# A4a_ESP32-S3-WROOM-1_1_0.net
KiCad netlist of a schematic drawn in EAGLE
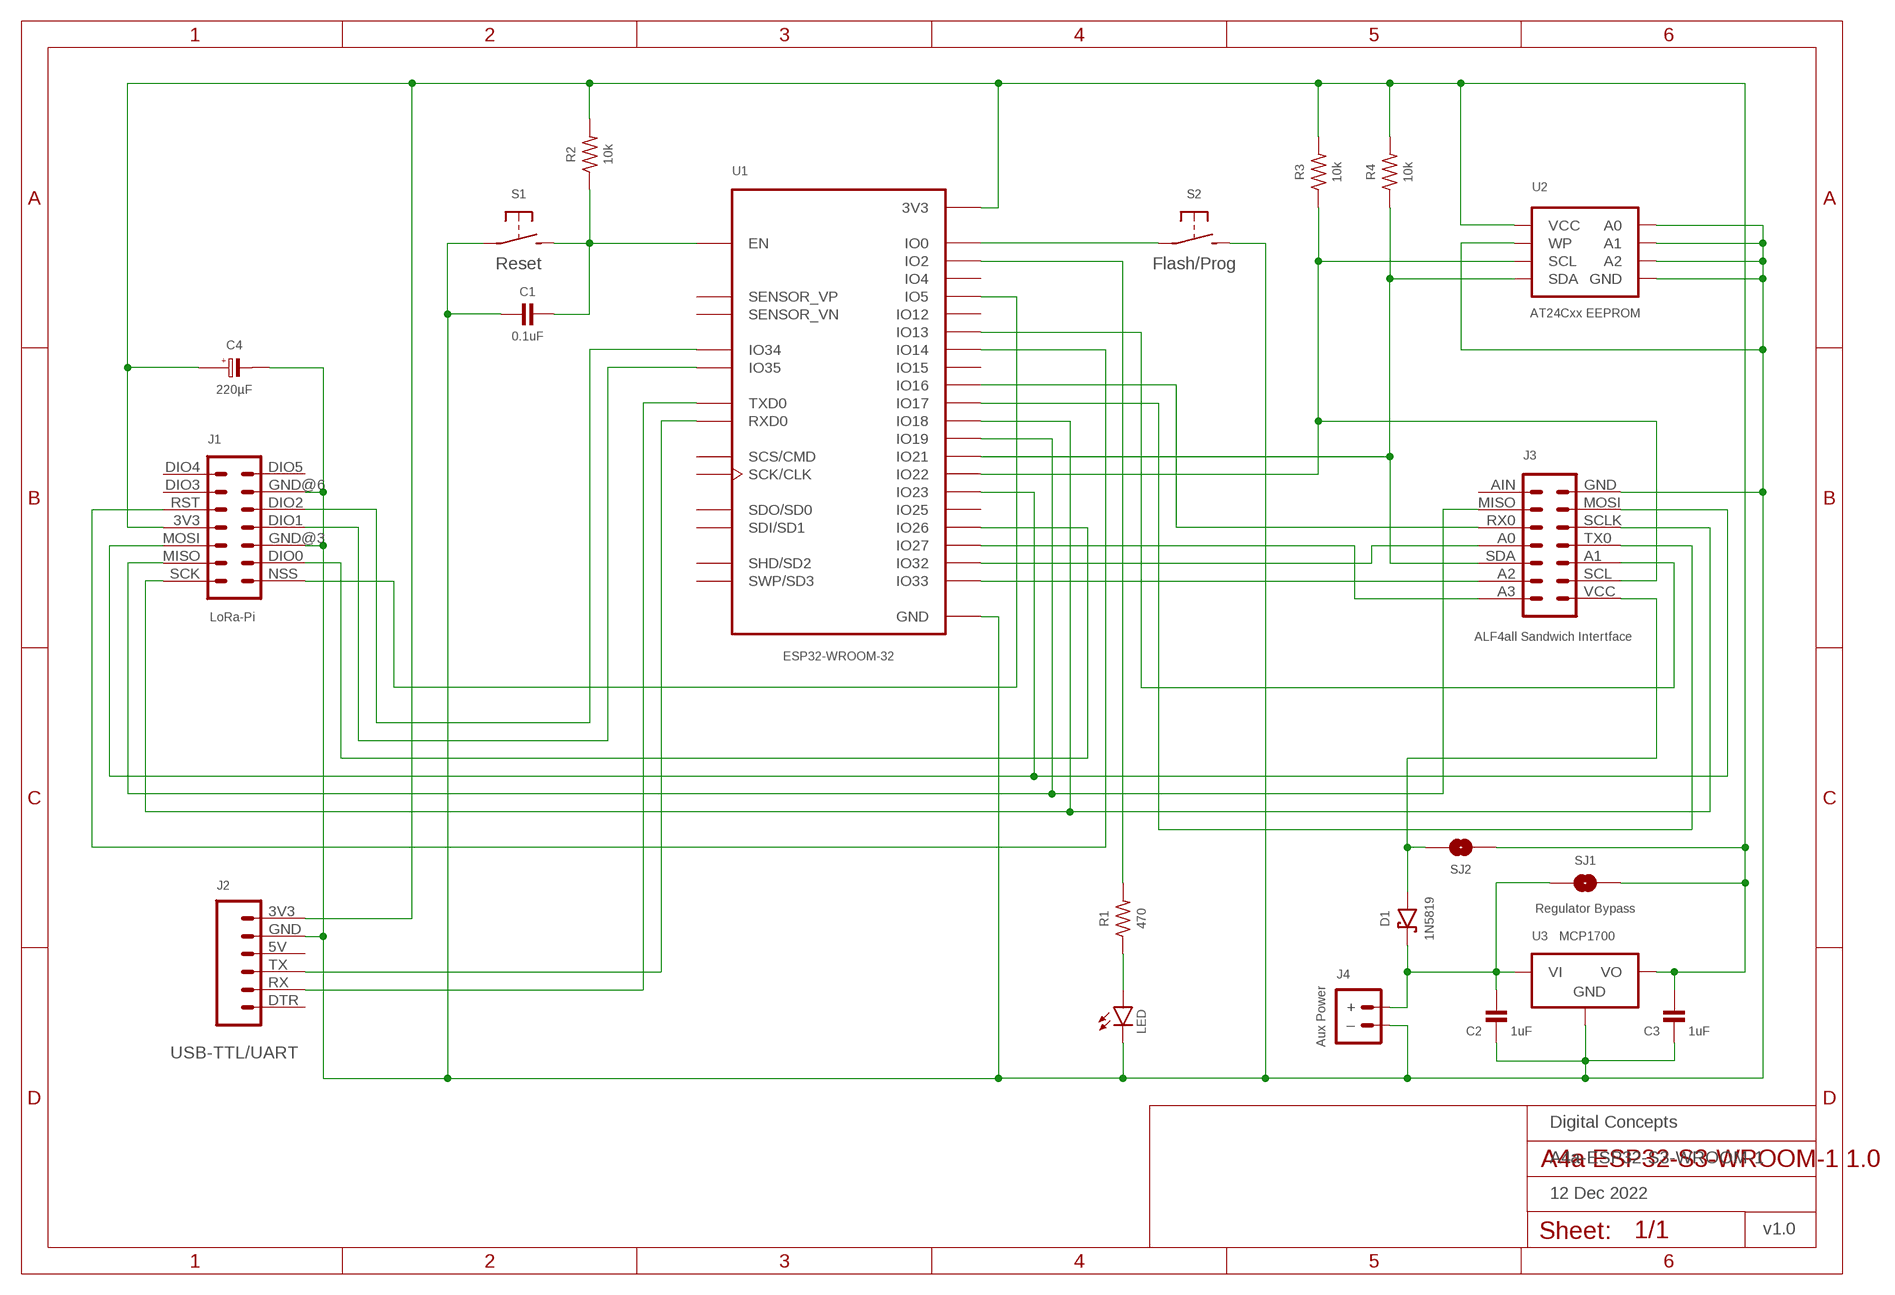
[diagram p0: schematic, sheet 1]

(export (version "E")
  (design (tool "Eeschema 10.0.6"))
  (components
    (comp (ref "C1")
      (value "0.1uF")
      (footprint "eagle-import:C0805@1")
      (libsource (lib "eagle-import") (part "CAPACITOR"))
    )
    (comp (ref "C2")
      (value "1uF")
      (footprint "eagle-import:C0805@1")
      (libsource (lib "eagle-import") (part "CAPACITOR"))
    )
    (comp (ref "C3")
      (value "1uF")
      (footprint "eagle-import:C0805@1")
      (libsource (lib "eagle-import") (part "CAPACITOR"))
    )
    (comp (ref "C4")
      (value "220µF")
      (footprint "eagle-import:C3528-21")
      (libsource (lib "eagle-import") (part "CAPACITOR-TANTALUM-3528"))
    )
    (comp (ref "D1")
      (value "1N5819")
      (footprint "eagle-import:SOD-123")
      (libsource (lib "eagle-import") (part "DIODE-SCHOTTKY-1N5819"))
    )
    (comp (ref "J1")
      (value "LoRa-Pi")
      (footprint "eagle-import:RFM95W-PI")
      (libsource (lib "eagle-import") (part "RFM95W-PI-HEADER"))
    )
    (comp (ref "J2")
      (value "USB-TTL/UART")
      (footprint "eagle-import:CONN_06-UART")
      (libsource (lib "eagle-import") (part "HEADER-1X6-UART"))
    )
    (comp (ref "J3")
      (value "ALF4all Sandwich Intertface")
      (footprint "eagle-import:CONN_2X7-ALF4ALL-PROCESSOR-B")
      (libsource (lib "eagle-import") (part "HEADER-2X7-ALF4ALL-PROCESSOR-B"))
    )
    (comp (ref "J4")
      (value "Aux Power")
      (footprint "eagle-import:JST-PH2.0-2-HORIZONTAL")
      (libsource (lib "eagle-import") (part "JST-PH2.0-2-MALE-HORIZONTALJST-PTH-2"))
    )
    (comp (ref "LED")
      (value "LEDCHIP-LED0805")
      (footprint "eagle-import:CHIP-LED0805")
      (libsource (lib "eagle-import") (part "LEDCHIP-LED0805"))
    )
    (comp (ref "R1")
      (value "470")
      (footprint "eagle-import:R0805")
      (libsource (lib "eagle-import") (part "RESISTORR0805"))
    )
    (comp (ref "R2")
      (value "10k")
      (footprint "eagle-import:R0805")
      (libsource (lib "eagle-import") (part "RESISTORR0805"))
    )
    (comp (ref "R3")
      (value "10k")
      (footprint "eagle-import:R0805")
      (libsource (lib "eagle-import") (part "RESISTORR0805"))
    )
    (comp (ref "R4")
      (value "10k")
      (footprint "eagle-import:R0805")
      (libsource (lib "eagle-import") (part "RESISTORR0805"))
    )
    (comp (ref "S1")
      (value "Reset")
      (footprint "eagle-import:SWITCH-2-PAD")
      (libsource (lib "eagle-import") (part "SWITCH-MOMENTARY-2-PIN"))
    )
    (comp (ref "S2")
      (value "Flash/Prog")
      (footprint "eagle-import:SWITCH-2-PAD")
      (libsource (lib "eagle-import") (part "SWITCH-MOMENTARY-2-PIN"))
    )
    (comp (ref "SJ1")
      (value "Regulator Bypass")
      (footprint "eagle-import:SJ")
      (libsource (lib "eagle-import") (part "SJ"))
    )
    (comp (ref "SJ2") (value "SJ") (footprint "eagle-import:SJ") (libsource (lib "eagle-import") (part "SJ")))
    (comp (ref "U1")
      (value "ESP32-WROOM-32")
      (footprint "eagle-import:ESP32-WROOM-32")
      (libsource (lib "eagle-import") (part "ESP32-WROOM-32"))
    )
    (comp (ref "U2")
      (value "AT24Cxx EEPROM")
      (footprint "eagle-import:SOP-8")
      (libsource (lib "eagle-import") (part "AT24CXX-EEPROM"))
    )
    (comp (ref "U3")
      (value "MCP1700")
      (footprint "eagle-import:SOT-23-3")
      (libsource (lib "eagle-import") (part "MCP1700"))
    )
  )
  (nets
    (net (code "1") (name "Net-(C4-+)") (class "Default")
      (node (ref "C3") (pin "1") (pinfunction "1_1") (pintype "passive"))
      (node (ref "C4") (pin "1") (pinfunction "+_1") (pintype "passive"))
      (node (ref "J1") (pin "3V3") (pinfunction "11_3V3") (pintype "passive"))
      (node (ref "J2") (pin "3V3") (pinfunction "6_3V3") (pintype "passive"))
      (node (ref "R2") (pin "2") (pinfunction "2_2") (pintype "passive"))
      (node (ref "R3") (pin "2") (pinfunction "2_2") (pintype "passive"))
      (node (ref "R4") (pin "2") (pinfunction "2_2") (pintype "passive"))
      (node (ref "SJ1") (pin "2") (pinfunction "2_2") (pintype "passive"))
      (node (ref "SJ2") (pin "2") (pinfunction "2_2") (pintype "passive"))
      (node (ref "U1") (pin "3V3") (pinfunction "3V3_3V3") (pintype "power_in"))
      (node (ref "U2") (pin "P$8") (pinfunction "VCC_P$8") (pintype "bidirectional"))
      (node (ref "U3") (pin "2") (pinfunction "VO_2") (pintype "output"))
    )
    (net (code "2") (name "Net-(C4--)") (class "Default")
      (node (ref "C1") (pin "2") (pinfunction "2_2") (pintype "passive"))
      (node (ref "C2") (pin "2") (pinfunction "2_2") (pintype "passive"))
      (node (ref "C3") (pin "2") (pinfunction "2_2") (pintype "passive"))
      (node (ref "C4") (pin "2") (pinfunction "-_2") (pintype "passive"))
      (node (ref "J1") (pin "GND@3") (pinfunction "3_GND@3") (pintype "passive"))
      (node (ref "J1") (pin "GND@6") (pinfunction "6_GND@6") (pintype "passive"))
      (node (ref "J2") (pin "GND") (pinfunction "5_GND") (pintype "passive"))
      (node (ref "J3") (pin "GND") (pinfunction "7_GND") (pintype "passive"))
      (node (ref "J4") (pin "-") (pinfunction "–_-") (pintype "power_in"))
      (node (ref "LED") (pin "C") (pinfunction "C_C") (pintype "passive"))
      (node (ref "S1") (pin "P$1") (pinfunction "P_P$1") (pintype "passive"))
      (node (ref "S2") (pin "P$2") (pinfunction "S_P$2") (pintype "passive"))
      (node (ref "U1") (pin "GND@1") (pinfunction "GND_GND@1") (pintype "power_in"))
      (node (ref "U1") (pin "GND@15") (pinfunction "GND_GND@15") (pintype "power_in"))
      (node (ref "U1") (pin "GND@38") (pinfunction "GND_GND@38") (pintype "power_in"))
      (node (ref "U1") (pin "TP") (pinfunction "GND_TP") (pintype "power_in"))
      (node (ref "U1") (pin "TP@P1") (pinfunction "GND_TP@P1") (pintype "power_in"))
      (node (ref "U1") (pin "TP@P2") (pinfunction "GND_TP@P2") (pintype "power_in"))
      (node (ref "U1") (pin "TP@P3") (pinfunction "GND_TP@P3") (pintype "power_in"))
      (node (ref "U1") (pin "TP@P4") (pinfunction "GND_TP@P4") (pintype "power_in"))
      (node (ref "U1") (pin "TP@P5") (pinfunction "GND_TP@P5") (pintype "power_in"))
      (node (ref "U1") (pin "TP@P6") (pinfunction "GND_TP@P6") (pintype "power_in"))
      (node (ref "U1") (pin "TP@P7") (pinfunction "GND_TP@P7") (pintype "power_in"))
      (node (ref "U1") (pin "TP@P8") (pinfunction "GND_TP@P8") (pintype "power_in"))
      (node (ref "U1") (pin "TP@P9") (pinfunction "GND_TP@P9") (pintype "power_in"))
      (node (ref "U1") (pin "TP@V1") (pinfunction "GND_TP@V1") (pintype "power_in"))
      (node (ref "U1") (pin "TP@V10") (pinfunction "GND_TP@V10") (pintype "power_in"))
      (node (ref "U1") (pin "TP@V11") (pinfunction "GND_TP@V11") (pintype "power_in"))
      (node (ref "U1") (pin "TP@V12") (pinfunction "GND_TP@V12") (pintype "power_in"))
      (node (ref "U1") (pin "TP@V2") (pinfunction "GND_TP@V2") (pintype "power_in"))
      (node (ref "U1") (pin "TP@V3") (pinfunction "GND_TP@V3") (pintype "power_in"))
      (node (ref "U1") (pin "TP@V4") (pinfunction "GND_TP@V4") (pintype "power_in"))
      (node (ref "U1") (pin "TP@V5") (pinfunction "GND_TP@V5") (pintype "power_in"))
      (node (ref "U1") (pin "TP@V6") (pinfunction "GND_TP@V6") (pintype "power_in"))
      (node (ref "U1") (pin "TP@V7") (pinfunction "GND_TP@V7") (pintype "power_in"))
      (node (ref "U1") (pin "TP@V8") (pinfunction "GND_TP@V8") (pintype "power_in"))
      (node (ref "U1") (pin "TP@V9") (pinfunction "GND_TP@V9") (pintype "power_in"))
      (node (ref "U1") (pin "TP@VP5") (pinfunction "GND_TP@VP5") (pintype "power_in"))
      (node (ref "U2") (pin "P$1") (pinfunction "A0_P$1") (pintype "bidirectional"))
      (node (ref "U2") (pin "P$2") (pinfunction "A1_P$2") (pintype "bidirectional"))
      (node (ref "U2") (pin "P$3") (pinfunction "A2_P$3") (pintype "bidirectional"))
      (node (ref "U2") (pin "P$4") (pinfunction "GND_P$4") (pintype "bidirectional"))
      (node (ref "U2") (pin "P$7") (pinfunction "WP_P$7") (pintype "bidirectional"))
      (node (ref "U3") (pin "1") (pinfunction "GND_1") (pintype "passive"))
    )
    (net (code "3") (name "Net-(J1-1)") (class "Default")
      (node (ref "J1") (pin "NSS") (pinfunction "1_NSS") (pintype "passive"))
      (node (ref "U1") (pin "IO5") (pinfunction "IO5_IO5") (pintype "bidirectional"))
    )
    (net (code "4") (name "Net-(J1-2)") (class "Default")
      (node (ref "J1") (pin "DIO0") (pinfunction "2_DIO0") (pintype "passive"))
      (node (ref "U1") (pin "IO26") (pinfunction "IO26_IO26") (pintype "bidirectional"))
    )
    (net (code "5") (name "Net-(J1-4)") (class "Default")
      (node (ref "J1") (pin "DIO1") (pinfunction "4_DIO1") (pintype "passive"))
      (node (ref "U1") (pin "IO35") (pinfunction "IO35_IO35") (pintype "input"))
    )
    (net (code "6") (name "Net-(J1-5)") (class "Default")
      (node (ref "J1") (pin "DIO2") (pinfunction "5_DIO2") (pintype "passive"))
      (node (ref "U1") (pin "IO34") (pinfunction "IO34_IO34") (pintype "input"))
    )
    (net (code "7") (name "Net-(J1-10)") (class "Default")
      (node (ref "J1") (pin "RST") (pinfunction "10_RST") (pintype "passive"))
      (node (ref "U1") (pin "IO14") (pinfunction "IO14_IO14") (pintype "bidirectional"))
    )
    (net (code "8") (name "Net-(J1-12)") (class "Default")
      (node (ref "J1") (pin "MOSI") (pinfunction "12_MOSI") (pintype "passive"))
      (node (ref "J3") (pin "MOSI") (pinfunction "6_MOSI") (pintype "passive"))
      (node (ref "U1") (pin "IO23") (pinfunction "IO23_IO23") (pintype "bidirectional"))
    )
    (net (code "9") (name "Net-(J1-13)") (class "Default")
      (node (ref "J1") (pin "MISO") (pinfunction "13_MISO") (pintype "passive"))
      (node (ref "J3") (pin "MISO") (pinfunction "9_MISO") (pintype "passive"))
      (node (ref "U1") (pin "IO19") (pinfunction "IO19_IO19") (pintype "bidirectional"))
    )
    (net (code "10") (name "Net-(J1-14)") (class "Default")
      (node (ref "J1") (pin "SCK") (pinfunction "14_SCK") (pintype "passive"))
      (node (ref "J3") (pin "SCLK") (pinfunction "5_SCLK") (pintype "passive"))
      (node (ref "U1") (pin "IO18") (pinfunction "IO18_IO18") (pintype "bidirectional"))
    )
    (net (code "11") (name "Net-(J2-2)") (class "Default")
      (node (ref "J2") (pin "RX") (pinfunction "2_RX") (pintype "passive"))
      (node (ref "U1") (pin "TXD0") (pinfunction "TXD0_TXD0") (pintype "bidirectional"))
    )
    (net (code "12") (name "Net-(J2-3)") (class "Default")
      (node (ref "J2") (pin "TX") (pinfunction "3_TX") (pintype "passive"))
      (node (ref "U1") (pin "RXD0") (pinfunction "RXD0_RXD0") (pintype "bidirectional"))
    )
    (net (code "13") (name "Net-(J3-1)") (class "Default")
      (node (ref "D1") (pin "A") (pinfunction "A_A") (pintype "passive"))
      (node (ref "J3") (pin "VCC") (pinfunction "1_VCC") (pintype "passive"))
      (node (ref "SJ2") (pin "1") (pinfunction "1_1") (pintype "passive"))
    )
    (net (code "14") (name "Net-(J3-2)") (class "Default")
      (node (ref "J3") (pin "SCL") (pinfunction "2_SCL") (pintype "passive"))
      (node (ref "R3") (pin "1") (pinfunction "1_1") (pintype "passive"))
      (node (ref "U1") (pin "IO22") (pinfunction "IO22_IO22") (pintype "bidirectional"))
      (node (ref "U2") (pin "P$6") (pinfunction "SCL_P$6") (pintype "bidirectional"))
    )
    (net (code "15") (name "Net-(J3-3)") (class "Default")
      (node (ref "J3") (pin "A1") (pinfunction "3_A1") (pintype "passive"))
      (node (ref "U1") (pin "IO13") (pinfunction "IO13_IO13") (pintype "bidirectional"))
    )
    (net (code "16") (name "Net-(J3-4)") (class "Default")
      (node (ref "J3") (pin "TX0") (pinfunction "4_TX0") (pintype "passive"))
      (node (ref "U1") (pin "IO17") (pinfunction "IO17_IO17") (pintype "bidirectional"))
    )
    (net (code "17") (name "Net-(J3-10)") (class "Default")
      (node (ref "J3") (pin "RX0") (pinfunction "10_RX0") (pintype "passive"))
      (node (ref "U1") (pin "IO16") (pinfunction "IO16_IO16") (pintype "bidirectional"))
    )
    (net (code "18") (name "Net-(J3-11)") (class "Default")
      (node (ref "J3") (pin "A0") (pinfunction "11_A0") (pintype "passive"))
      (node (ref "U1") (pin "IO32") (pinfunction "IO32_IO32") (pintype "bidirectional"))
    )
    (net (code "19") (name "Net-(J3-12)") (class "Default")
      (node (ref "J3") (pin "SDA") (pinfunction "12_SDA") (pintype "passive"))
      (node (ref "R4") (pin "1") (pinfunction "1_1") (pintype "passive"))
      (node (ref "U1") (pin "IO21") (pinfunction "IO21_IO21") (pintype "bidirectional"))
      (node (ref "U2") (pin "P$5") (pinfunction "SDA_P$5") (pintype "bidirectional"))
    )
    (net (code "20") (name "Net-(J3-13)") (class "Default")
      (node (ref "J3") (pin "A2") (pinfunction "13_A2") (pintype "passive"))
      (node (ref "U1") (pin "IO33") (pinfunction "IO33_IO33") (pintype "bidirectional"))
    )
    (net (code "21") (name "Net-(J3-14)") (class "Default")
      (node (ref "J3") (pin "A3") (pinfunction "14_A3") (pintype "passive"))
      (node (ref "U1") (pin "IO27") (pinfunction "IO27_IO27") (pintype "bidirectional"))
    )
    (net (code "22") (name "Net-(LED-PadA)") (class "Default")
      (node (ref "LED") (pin "A") (pinfunction "A_A") (pintype "passive"))
      (node (ref "R1") (pin "1") (pinfunction "1_1") (pintype "passive"))
    )
    (net (code "23") (name "Net-(R1-Pad2)") (class "Default")
      (node (ref "R1") (pin "2") (pinfunction "2_2") (pintype "passive"))
      (node (ref "U1") (pin "IO2") (pinfunction "IO2_IO2") (pintype "bidirectional"))
    )
    (net (code "24") (name "Net-(S1-S)") (class "Default")
      (node (ref "C1") (pin "1") (pinfunction "1_1") (pintype "passive"))
      (node (ref "R2") (pin "1") (pinfunction "1_1") (pintype "passive"))
      (node (ref "S1") (pin "P$2") (pinfunction "S_P$2") (pintype "passive"))
      (node (ref "U1") (pin "EN") (pinfunction "EN_EN") (pintype "input"))
    )
    (net (code "25") (name "Net-(S2-P)") (class "Default")
      (node (ref "S2") (pin "P$1") (pinfunction "P_P$1") (pintype "passive"))
      (node (ref "U1") (pin "IO0") (pinfunction "IO0_IO0") (pintype "bidirectional"))
    )
    (net (code "26") (name "Net-(U3-VI)") (class "Default")
      (node (ref "C2") (pin "1") (pinfunction "1_1") (pintype "passive"))
      (node (ref "D1") (pin "C") (pinfunction "C_C") (pintype "passive"))
      (node (ref "J4") (pin "+") (pinfunction "+_+") (pintype "power_in"))
      (node (ref "SJ1") (pin "1") (pinfunction "1_1") (pintype "passive"))
      (node (ref "U3") (pin "3") (pinfunction "VI_3") (pintype "input"))
    )
    (net (code "27") (name "unconnected-(J1-7-PadDIO5)") (class "Default")
      (node (ref "J1") (pin "DIO5") (pinfunction "7_DIO5") (pintype "passive"))
    )
    (net (code "28") (name "unconnected-(J1-8-PadDIO4)") (class "Default")
      (node (ref "J1") (pin "DIO4") (pinfunction "8_DIO4") (pintype "passive"))
    )
    (net (code "29") (name "unconnected-(J1-9-PadDIO3)") (class "Default")
      (node (ref "J1") (pin "DIO3") (pinfunction "9_DIO3") (pintype "passive"))
    )
    (net (code "30") (name "unconnected-(J2-1-PadDTR)") (class "Default")
      (node (ref "J2") (pin "DTR") (pinfunction "1_DTR") (pintype "passive"))
    )
    (net (code "31") (name "unconnected-(J2-4-Pad5V)") (class "Default")
      (node (ref "J2") (pin "5V") (pinfunction "4_5V") (pintype "passive"))
    )
    (net (code "32") (name "unconnected-(J3-8-PadAIN)") (class "Default")
      (node (ref "J3") (pin "AIN") (pinfunction "8_AIN") (pintype "passive"))
    )
    (net (code "33") (name "unconnected-(U1-PadIO4)") (class "Default")
      (node (ref "U1") (pin "IO4") (pinfunction "IO4_IO4") (pintype "bidirectional"))
    )
    (net (code "34") (name "unconnected-(U1-PadIO12)") (class "Default")
      (node (ref "U1") (pin "IO12") (pinfunction "IO12_IO12") (pintype "bidirectional"))
    )
    (net (code "35") (name "unconnected-(U1-PadIO15)") (class "Default")
      (node (ref "U1") (pin "IO15") (pinfunction "IO15_IO15") (pintype "bidirectional"))
    )
    (net (code "36") (name "unconnected-(U1-PadIO25)") (class "Default")
      (node (ref "U1") (pin "IO25") (pinfunction "IO25_IO25") (pintype "bidirectional"))
    )
    (net (code "37") (name "unconnected-(U1-PadSENSOR_VN)") (class "Default")
      (node (ref "U1") (pin "SENSOR_VN") (pinfunction "SENSOR_VN_SENSOR_VN") (pintype "input"))
    )
    (net (code "38") (name "unconnected-(U1-PadSENSOR_VP)") (class "Default")
      (node (ref "U1") (pin "SENSOR_VP") (pinfunction "SENSOR_VP_SENSOR_VP") (pintype "input"))
    )
    (net (code "39") (name "unconnected-(U1-SCK{slash}CLK-PadCLK)") (class "Default")
      (node (ref "U1") (pin "CLK") (pinfunction "SCK/CLK_CLK") (pintype "bidirectional"))
    )
    (net (code "40") (name "unconnected-(U1-SCS{slash}CMD-PadCMD)") (class "Default")
      (node (ref "U1") (pin "CMD") (pinfunction "SCS/CMD_CMD") (pintype "bidirectional"))
    )
    (net (code "41") (name "unconnected-(U1-SDI{slash}SD1-PadSD1)") (class "Default")
      (node (ref "U1") (pin "SD1") (pinfunction "SDI/SD1_SD1") (pintype "bidirectional"))
    )
    (net (code "42") (name "unconnected-(U1-SDO{slash}SD0-PadSD0)") (class "Default")
      (node (ref "U1") (pin "SD0") (pinfunction "SDO/SD0_SD0") (pintype "bidirectional"))
    )
    (net (code "43") (name "unconnected-(U1-SHD{slash}SD2-PadSD2)") (class "Default")
      (node (ref "U1") (pin "SD2") (pinfunction "SHD/SD2_SD2") (pintype "bidirectional"))
    )
    (net (code "44") (name "unconnected-(U1-SWP{slash}SD3-PadSD3)") (class "Default")
      (node (ref "U1") (pin "SD3") (pinfunction "SWP/SD3_SD3") (pintype "bidirectional"))
    )
  )
)
